# MCU_64.net
KiCad netlist of a schematic drawn in Altium Designer
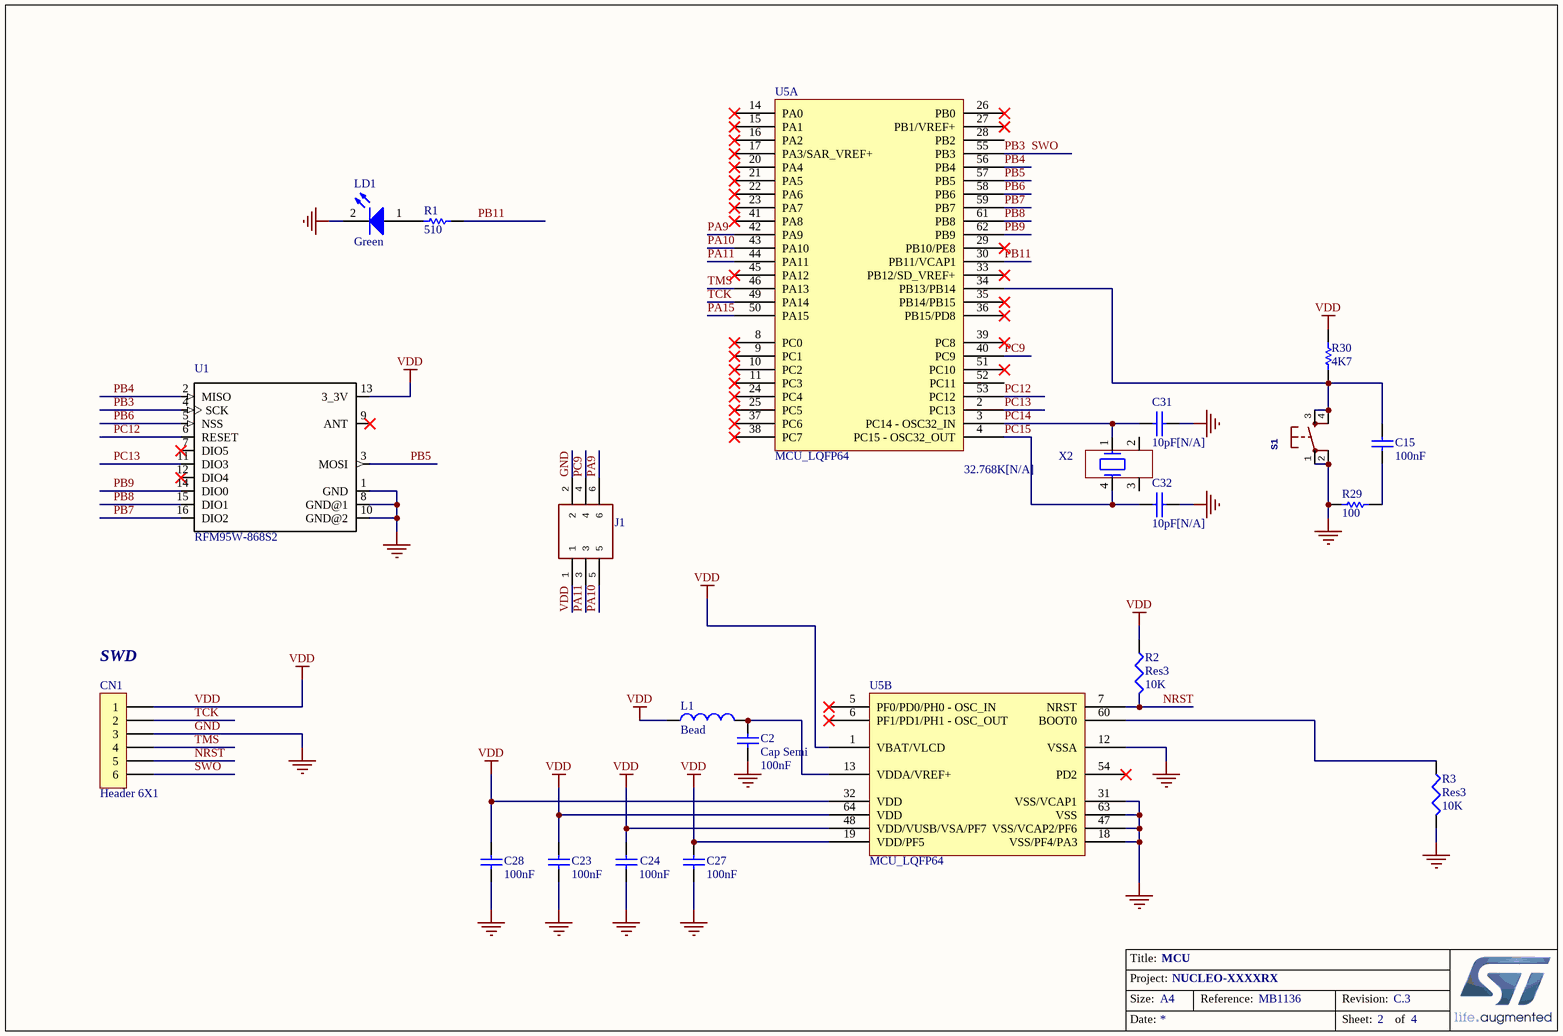
[diagram p0: MCU_64.SchDoc]

(export (version "E")
  (design (tool "Eeschema 10.0.6"))
  (components
    (comp (ref "C2")
      (value "Cap Semi")
      (footprint "1608[0603]")
      (description "Capacitor (Semiconductor SIM Model)")
      (fields (field (name "ALTIUM_VALUE") "100nF") (field (name "PUBLISHER") "Altium Limited"))
      (libsource (lib "Miscellaneous Devices") (part "Cap Semi"))
    )
    (comp (ref "C15")
      (value "100nF")
      (footprint "RAD-0.3")
      (description "Capacitor")
      (fields (field (name "PUBLISHER") "Altium Limited"))
      (libsource (lib "Miscellaneous Devices") (part "CAP"))
    )
    (comp (ref "C23")
      (value "100nF")
      (footprint "0603C")
      (description "Capacitor")
      (fields (field (name "PUBLISHER") "Altium Limited"))
      (libsource (lib "Miscellaneous Devices") (part "Cap"))
    )
    (comp (ref "C24")
      (value "100nF")
      (footprint "0603C")
      (description "Capacitor")
      (fields (field (name "PUBLISHER") "Altium Limited"))
      (libsource (lib "Miscellaneous Devices") (part "Cap"))
    )
    (comp (ref "C27")
      (value "100nF")
      (footprint "0603C")
      (description "Capacitor")
      (fields (field (name "PUBLISHER") "Altium Limited"))
      (libsource (lib "Miscellaneous Devices") (part "Cap"))
    )
    (comp (ref "C28")
      (value "100nF")
      (footprint "0603C")
      (description "Capacitor")
      (fields (field (name "PUBLISHER") "Altium Limited"))
      (libsource (lib "Miscellaneous Devices") (part "Cap"))
    )
    (comp (ref "C31")
      (value "10pF[N/A]")
      (footprint "0603C")
      (description "Capacitor")
      (libsource (lib "*") (part "CAP"))
    )
    (comp (ref "C32")
      (value "10pF[N/A]")
      (footprint "0603C")
      (description "Capacitor")
      (libsource (lib "*") (part "CAP"))
    )
    (comp (ref "CN1")
      (value "Header 6X1")
      (footprint "1*6P")
      (description "Header, 6-Pin, Single row")
      (fields (field (name "PUBLISHER") "Altium Limited"))
      (libsource (lib "Nucleo_64") (part "Header 6X1"))
    )
    (comp (ref "J1")
      (value "PIN-HEAD-1.27MM-2X03")
      (footprint "PIN-HEAD-1.27MM-2X03")
      (libsource (lib "WSense-conn-library") (part "PIN-HEAD-1.27MM-2X03"))
    )
    (comp (ref "L1")
      (value "Bead")
      (footprint "INDC1608L")
      (description "Inductor")
      (fields (field (name "PUBLISHER") "Altium Limited"))
      (libsource (lib "Miscellaneous Devices") (part "Inductor"))
    )
    (comp (ref "LD1")
      (value "Green")
      (footprint "0603D")
      (description "Typical RED, GREEN, YELLOW, AMBER GaAs LED")
      (fields (field (name "PUBLISHER") "Altium Limited"))
      (libsource (lib "Miscellaneous Devices") (part "LED2"))
    )
    (comp (ref "R1")
      (value "510")
      (footprint "0603R")
      (description "Resistor")
      (fields (field (name "PUBLISHER") "Altium Limited"))
      (libsource (lib "Miscellaneous Devices") (part "Res1"))
    )
    (comp (ref "R2")
      (value "Res3")
      (footprint "J1-0603")
      (description "Resistor")
      (fields (field (name "ALTIUM_VALUE") "10K") (field (name "PUBLISHER") "Altium Limited"))
      (libsource (lib "Miscellaneous Devices") (part "Res3"))
    )
    (comp (ref "R3")
      (value "Res3")
      (footprint "J1-0603")
      (description "Resistor")
      (fields (field (name "ALTIUM_VALUE") "10K") (field (name "PUBLISHER") "Altium Limited"))
      (libsource (lib "Miscellaneous Devices") (part "Res3"))
    )
    (comp (ref "R29")
      (value "100")
      (footprint "0603R")
      (description "Resistor")
      (fields (field (name "PUBLISHER") "Altium Limited"))
      (libsource (lib "Miscellaneous Devices") (part "Res1"))
    )
    (comp (ref "R30")
      (value "4K7")
      (footprint "0603R")
      (description "Resistor")
      (fields (field (name "PUBLISHER") "Altium Limited"))
      (libsource (lib "Miscellaneous Devices") (part "res1"))
    )
    (comp (ref "S1")
      (value "~")
      (footprint "TACTILE_SWITCH_SMD")
      (libsource (lib "WSense-conn-library") (part "TAC_SWITCHSND"))
    )
    (comp (ref "U1")
      (value "RFM95W-868S2")
      (footprint "XCVR_RFM95W-868S2")
      (fields (field (name "MF") "Hope Microelectronics"))
      (libsource (lib "RFM95W-868S2") (part "RFM95W-868S2"))
    )
    (comp (ref "U5")
      (value "MCU_LQFP64")
      (footprint "LQFP64")
      (libsource (lib "Nucleo_64") (part "MCU_LQFP64"))
    )
    (comp (ref "X2") (value "32.768K[N/A]") (footprint "XTAL_4SM_8X3R8") (libsource (lib "*") (part "MC306")))
  )
  (nets
    (net (code "1") (name "/NRST") (class "Default")
      (node (ref "CN1") (pin "5") (pinfunction "5_5") (pintype "passive"))
      (node (ref "R2") (pin "2") (pinfunction "2_2") (pintype "passive"))
      (node (ref "U5") (pin "7") (pinfunction "NRST_7") (pintype "passive"))
    )
    (net (code "2") (name "/PA9") (class "Default")
      (node (ref "J1") (pin "6") (pinfunction "6_6") (pintype "passive"))
      (node (ref "U5") (pin "42") (pinfunction "PA9_42") (pintype "passive"))
    )
    (net (code "3") (name "/PA10") (class "Default")
      (node (ref "J1") (pin "5") (pinfunction "5_5") (pintype "passive"))
      (node (ref "U5") (pin "43") (pinfunction "PA10_43") (pintype "passive"))
    )
    (net (code "4") (name "/PA11") (class "Default")
      (node (ref "J1") (pin "3") (pinfunction "3_3") (pintype "passive"))
      (node (ref "U5") (pin "44") (pinfunction "PA11_44") (pintype "passive"))
    )
    (net (code "5") (name "/PA15") (class "Default")
      (node (ref "U5") (pin "50") (pinfunction "PA15_50") (pintype "passive"))
    )
    (net (code "6") (name "/PB3") (class "Default")
      (node (ref "CN1") (pin "6") (pinfunction "6_6") (pintype "passive"))
      (node (ref "U1") (pin "4") (pinfunction "SCK_4") (pintype "input"))
      (node (ref "U5") (pin "55") (pinfunction "PB3_55") (pintype "passive"))
    )
    (net (code "7") (name "/PB4") (class "Default")
      (node (ref "U1") (pin "2") (pinfunction "MISO_2") (pintype "input"))
      (node (ref "U5") (pin "56") (pinfunction "PB4_56") (pintype "passive"))
    )
    (net (code "8") (name "/PB5") (class "Default")
      (node (ref "U1") (pin "3") (pinfunction "MOSI_3") (pintype "output"))
      (node (ref "U5") (pin "57") (pinfunction "PB5_57") (pintype "passive"))
    )
    (net (code "9") (name "/PB6") (class "Default")
      (node (ref "U1") (pin "5") (pinfunction "NSS_5") (pintype "input"))
      (node (ref "U5") (pin "58") (pinfunction "PB6_58") (pintype "passive"))
    )
    (net (code "10") (name "/PB7") (class "Default")
      (node (ref "U1") (pin "16") (pinfunction "DIO2_16") (pintype "bidirectional"))
      (node (ref "U5") (pin "59") (pinfunction "PB7_59") (pintype "passive"))
    )
    (net (code "11") (name "/PB8") (class "Default")
      (node (ref "U1") (pin "15") (pinfunction "DIO1_15") (pintype "bidirectional"))
      (node (ref "U5") (pin "61") (pinfunction "PB8_61") (pintype "passive"))
    )
    (net (code "12") (name "/PB9") (class "Default")
      (node (ref "U1") (pin "14") (pinfunction "DIO0_14") (pintype "bidirectional"))
      (node (ref "U5") (pin "62") (pinfunction "PB9_62") (pintype "passive"))
    )
    (net (code "13") (name "/PB11") (class "Default")
      (node (ref "R1") (pin "1") (pinfunction "1_1") (pintype "passive"))
      (node (ref "U5") (pin "30") (pinfunction "PB11/VCAP1_30") (pintype "passive"))
    )
    (net (code "14") (name "/PC9") (class "Default")
      (node (ref "J1") (pin "4") (pinfunction "4_4") (pintype "passive"))
      (node (ref "U5") (pin "40") (pinfunction "PC9_40") (pintype "passive"))
    )
    (net (code "15") (name "/PC12") (class "Default")
      (node (ref "U1") (pin "6") (pinfunction "RESET_6") (pintype "bidirectional"))
      (node (ref "U5") (pin "53") (pinfunction "PC12_53") (pintype "passive"))
    )
    (net (code "16") (name "/PC13") (class "Default")
      (node (ref "U1") (pin "11") (pinfunction "DIO3_11") (pintype "bidirectional"))
      (node (ref "U5") (pin "2") (pinfunction "PC13_2") (pintype "passive"))
    )
    (net (code "17") (name "/PC14") (class "Default")
      (node (ref "C31") (pin "1") (pinfunction "1_1") (pintype "passive"))
      (node (ref "U5") (pin "3") (pinfunction "PC14_-_OSC32_IN_3") (pintype "passive"))
      (node (ref "X2") (pin "1") (pinfunction "1_1") (pintype "passive"))
    )
    (net (code "18") (name "/PC15") (class "Default")
      (node (ref "C32") (pin "1") (pinfunction "1_1") (pintype "passive"))
      (node (ref "U5") (pin "4") (pinfunction "PC15_-_OSC32_OUT_4") (pintype "passive"))
      (node (ref "X2") (pin "4") (pinfunction "4_4") (pintype "passive"))
    )
    (net (code "19") (name "/TCK") (class "Default")
      (node (ref "CN1") (pin "2") (pinfunction "2_2") (pintype "passive"))
      (node (ref "U5") (pin "49") (pinfunction "PA14_49") (pintype "passive"))
    )
    (net (code "20") (name "/TMS") (class "Default")
      (node (ref "CN1") (pin "4") (pinfunction "4_4") (pintype "passive"))
      (node (ref "U5") (pin "46") (pinfunction "PA13_46") (pintype "passive"))
    )
    (net (code "21") (name "GND") (class "Default")
      (node (ref "C2") (pin "2") (pinfunction "2_2") (pintype "passive"))
      (node (ref "C23") (pin "2") (pinfunction "2_2") (pintype "passive"))
      (node (ref "C24") (pin "2") (pinfunction "2_2") (pintype "passive"))
      (node (ref "C27") (pin "2") (pinfunction "2_2") (pintype "passive"))
      (node (ref "C28") (pin "2") (pinfunction "2_2") (pintype "passive"))
      (node (ref "C31") (pin "2") (pinfunction "2_2") (pintype "passive"))
      (node (ref "C32") (pin "2") (pinfunction "2_2") (pintype "passive"))
      (node (ref "CN1") (pin "3") (pinfunction "3_3") (pintype "passive"))
      (node (ref "J1") (pin "2") (pinfunction "2_2") (pintype "passive"))
      (node (ref "LD1") (pin "2") (pinfunction "K_2") (pintype "passive"))
      (node (ref "R29") (pin "1") (pinfunction "1_1") (pintype "passive"))
      (node (ref "R3") (pin "2") (pinfunction "2_2") (pintype "passive"))
      (node (ref "S1") (pin "1") (pinfunction "1_1") (pintype "passive"))
      (node (ref "S1") (pin "2") (pinfunction "2_2") (pintype "passive"))
      (node (ref "U1") (pin "1") (pinfunction "GND_1") (pintype "power_in"))
      (node (ref "U1") (pin "10") (pinfunction "GND@2_10") (pintype "power_in"))
      (node (ref "U1") (pin "8") (pinfunction "GND@1_8") (pintype "power_in"))
      (node (ref "U5") (pin "12") (pinfunction "VSSA_12") (pintype "passive"))
      (node (ref "U5") (pin "18") (pinfunction "VSS/PF4/PA3_18") (pintype "passive"))
      (node (ref "U5") (pin "31") (pinfunction "VSS/VCAP1_31") (pintype "passive"))
      (node (ref "U5") (pin "47") (pinfunction "VSS/VCAP2/PF6_47") (pintype "passive"))
      (node (ref "U5") (pin "63") (pinfunction "VSS_63") (pintype "passive"))
    )
    (net (code "22") (name "Net-(C15-Pad1)") (class "Default")
      (node (ref "C15") (pin "1") (pinfunction "1_1") (pintype "passive"))
      (node (ref "R29") (pin "2") (pinfunction "2_2") (pintype "passive"))
    )
    (net (code "23") (name "Net-(LD1-A)") (class "Default")
      (node (ref "LD1") (pin "1") (pinfunction "A_1") (pintype "passive"))
      (node (ref "R1") (pin "2") (pinfunction "2_2") (pintype "passive"))
    )
    (net (code "24") (name "Net-(U5A-PB13{slash}PB14)") (class "Default")
      (node (ref "C15") (pin "2") (pinfunction "2_2") (pintype "passive"))
      (node (ref "R30") (pin "1") (pinfunction "1_1") (pintype "passive"))
      (node (ref "S1") (pin "3") (pinfunction "3_3") (pintype "passive"))
      (node (ref "S1") (pin "4") (pinfunction "4_4") (pintype "passive"))
      (node (ref "U5") (pin "34") (pinfunction "PB13/PB14_34") (pintype "passive"))
    )
    (net (code "25") (name "Net-(U5B-BOOT0)") (class "Default")
      (node (ref "R3") (pin "1") (pinfunction "1_1") (pintype "passive"))
      (node (ref "U5") (pin "60") (pinfunction "BOOT0_60") (pintype "passive"))
    )
    (net (code "26") (name "Net-(U5B-VDDA{slash}VREF+)") (class "Default")
      (node (ref "C2") (pin "1") (pinfunction "1_1") (pintype "passive"))
      (node (ref "L1") (pin "2") (pinfunction "2_2") (pintype "passive"))
      (node (ref "U5") (pin "13") (pinfunction "VDDA/VREF+_13") (pintype "passive"))
    )
    (net (code "27") (name "VDD") (class "Default")
      (node (ref "C23") (pin "1") (pinfunction "1_1") (pintype "passive"))
      (node (ref "C24") (pin "1") (pinfunction "1_1") (pintype "passive"))
      (node (ref "C27") (pin "1") (pinfunction "1_1") (pintype "passive"))
      (node (ref "C28") (pin "1") (pinfunction "1_1") (pintype "passive"))
      (node (ref "CN1") (pin "1") (pinfunction "1_1") (pintype "passive"))
      (node (ref "J1") (pin "1") (pinfunction "1_1") (pintype "passive"))
      (node (ref "L1") (pin "1") (pinfunction "1_1") (pintype "passive"))
      (node (ref "R2") (pin "1") (pinfunction "1_1") (pintype "passive"))
      (node (ref "R30") (pin "2") (pinfunction "2_2") (pintype "passive"))
      (node (ref "U1") (pin "13") (pinfunction "3_3V_13") (pintype "power_in"))
      (node (ref "U5") (pin "1") (pinfunction "VBAT/VLCD_1") (pintype "passive"))
      (node (ref "U5") (pin "19") (pinfunction "VDD/PF5_19") (pintype "passive"))
      (node (ref "U5") (pin "32") (pinfunction "VDD_32") (pintype "passive"))
      (node (ref "U5") (pin "48") (pinfunction "VDD/VUSB/VSA/PF7_48") (pintype "passive"))
      (node (ref "U5") (pin "64") (pinfunction "VDD_64") (pintype "passive"))
    )
    (net (code "28") (name "unconnected-(U1-ANT-Pad9)") (class "Default")
      (node (ref "U1") (pin "9") (pinfunction "ANT_9") (pintype "passive+no_connect"))
    )
    (net (code "29") (name "unconnected-(U1-DIO4-Pad12)") (class "Default")
      (node (ref "U1") (pin "12") (pinfunction "DIO4_12") (pintype "bidirectional+no_connect"))
    )
    (net (code "30") (name "unconnected-(U1-DIO5-Pad7)") (class "Default")
      (node (ref "U1") (pin "7") (pinfunction "DIO5_7") (pintype "bidirectional+no_connect"))
    )
    (net (code "31") (name "unconnected-(U5A-PA0-Pad14)") (class "Default")
      (node (ref "U5") (pin "14") (pinfunction "PA0_14") (pintype "passive+no_connect"))
    )
    (net (code "32") (name "unconnected-(U5A-PA1-Pad15)") (class "Default")
      (node (ref "U5") (pin "15") (pinfunction "PA1_15") (pintype "passive+no_connect"))
    )
    (net (code "33") (name "unconnected-(U5A-PA2-Pad16)") (class "Default")
      (node (ref "U5") (pin "16") (pinfunction "PA2_16") (pintype "passive+no_connect"))
    )
    (net (code "34") (name "unconnected-(U5A-PA3{slash}SAR_VREF+-Pad17)") (class "Default")
      (node (ref "U5") (pin "17") (pinfunction "PA3/SAR_VREF+_17") (pintype "passive+no_connect"))
    )
    (net (code "35") (name "unconnected-(U5A-PA4-Pad20)") (class "Default")
      (node (ref "U5") (pin "20") (pinfunction "PA4_20") (pintype "passive+no_connect"))
    )
    (net (code "36") (name "unconnected-(U5A-PA5-Pad21)") (class "Default")
      (node (ref "U5") (pin "21") (pinfunction "PA5_21") (pintype "passive+no_connect"))
    )
    (net (code "37") (name "unconnected-(U5A-PA6-Pad22)") (class "Default")
      (node (ref "U5") (pin "22") (pinfunction "PA6_22") (pintype "passive+no_connect"))
    )
    (net (code "38") (name "unconnected-(U5A-PA7-Pad23)") (class "Default")
      (node (ref "U5") (pin "23") (pinfunction "PA7_23") (pintype "passive+no_connect"))
    )
    (net (code "39") (name "unconnected-(U5A-PA8-Pad41)") (class "Default")
      (node (ref "U5") (pin "41") (pinfunction "PA8_41") (pintype "passive+no_connect"))
    )
    (net (code "40") (name "unconnected-(U5A-PA12-Pad45)") (class "Default")
      (node (ref "U5") (pin "45") (pinfunction "PA12_45") (pintype "passive+no_connect"))
    )
    (net (code "41") (name "unconnected-(U5A-PB0-Pad26)") (class "Default")
      (node (ref "U5") (pin "26") (pinfunction "PB0_26") (pintype "passive+no_connect"))
    )
    (net (code "42") (name "unconnected-(U5A-PB1{slash}VREF+-Pad27)") (class "Default")
      (node (ref "U5") (pin "27") (pinfunction "PB1/VREF+_27") (pintype "passive+no_connect"))
    )
    (net (code "43") (name "unconnected-(U5A-PB2-Pad28)") (class "Default")
      (node (ref "U5") (pin "28") (pinfunction "PB2_28") (pintype "passive"))
    )
    (net (code "44") (name "unconnected-(U5A-PB10{slash}PE8-Pad29)") (class "Default")
      (node (ref "U5") (pin "29") (pinfunction "PB10/PE8_29") (pintype "passive+no_connect"))
    )
    (net (code "45") (name "unconnected-(U5A-PB12{slash}SD_VREF+-Pad33)") (class "Default")
      (node (ref "U5") (pin "33") (pinfunction "PB12/SD_VREF+_33") (pintype "passive+no_connect"))
    )
    (net (code "46") (name "unconnected-(U5A-PB14{slash}PB15-Pad35)") (class "Default")
      (node (ref "U5") (pin "35") (pinfunction "PB14/PB15_35") (pintype "passive+no_connect"))
    )
    (net (code "47") (name "unconnected-(U5A-PB15{slash}PD8-Pad36)") (class "Default")
      (node (ref "U5") (pin "36") (pinfunction "PB15/PD8_36") (pintype "passive+no_connect"))
    )
    (net (code "48") (name "unconnected-(U5A-PC0-Pad8)") (class "Default")
      (node (ref "U5") (pin "8") (pinfunction "PC0_8") (pintype "passive+no_connect"))
    )
    (net (code "49") (name "unconnected-(U5A-PC1-Pad9)") (class "Default")
      (node (ref "U5") (pin "9") (pinfunction "PC1_9") (pintype "passive+no_connect"))
    )
    (net (code "50") (name "unconnected-(U5A-PC2-Pad10)") (class "Default")
      (node (ref "U5") (pin "10") (pinfunction "PC2_10") (pintype "passive+no_connect"))
    )
    (net (code "51") (name "unconnected-(U5A-PC3-Pad11)") (class "Default")
      (node (ref "U5") (pin "11") (pinfunction "PC3_11") (pintype "passive+no_connect"))
    )
    (net (code "52") (name "unconnected-(U5A-PC4-Pad24)") (class "Default")
      (node (ref "U5") (pin "24") (pinfunction "PC4_24") (pintype "passive+no_connect"))
    )
    (net (code "53") (name "unconnected-(U5A-PC5-Pad25)") (class "Default")
      (node (ref "U5") (pin "25") (pinfunction "PC5_25") (pintype "passive+no_connect"))
    )
    (net (code "54") (name "unconnected-(U5A-PC6-Pad37)") (class "Default")
      (node (ref "U5") (pin "37") (pinfunction "PC6_37") (pintype "passive+no_connect"))
    )
    (net (code "55") (name "unconnected-(U5A-PC7-Pad38)") (class "Default")
      (node (ref "U5") (pin "38") (pinfunction "PC7_38") (pintype "passive+no_connect"))
    )
    (net (code "56") (name "unconnected-(U5A-PC8-Pad39)") (class "Default")
      (node (ref "U5") (pin "39") (pinfunction "PC8_39") (pintype "passive+no_connect"))
    )
    (net (code "57") (name "unconnected-(U5A-PC10-Pad51)") (class "Default")
      (node (ref "U5") (pin "51") (pinfunction "PC10_51") (pintype "passive+no_connect"))
    )
    (net (code "58") (name "unconnected-(U5A-PC11-Pad52)") (class "Default")
      (node (ref "U5") (pin "52") (pinfunction "PC11_52") (pintype "passive"))
    )
    (net (code "59") (name "unconnected-(U5B-PD2-Pad54)") (class "Default")
      (node (ref "U5") (pin "54") (pinfunction "PD2_54") (pintype "passive+no_connect"))
    )
    (net (code "60") (name "unconnected-(U5B-PF0{slash}PD0{slash}PH0_-_OSC_IN-Pad5)") (class "Default")
      (node (ref "U5") (pin "5") (pinfunction "PF0/PD0/PH0_-_OSC_IN_5") (pintype "passive+no_connect"))
    )
    (net (code "61") (name "unconnected-(U5B-PF1{slash}PD1{slash}PH1_-_OSC_OUT-Pad6)") (class "Default")
      (node (ref "U5") (pin "6") (pinfunction "PF1/PD1/PH1_-_OSC_OUT_6") (pintype "passive+no_connect"))
    )
    (net (code "62") (name "unconnected-(X2-Pad2)") (class "Default")
      (node (ref "X2") (pin "2") (pinfunction "2_2") (pintype "passive"))
    )
    (net (code "63") (name "unconnected-(X2-Pad3)") (class "Default")
      (node (ref "X2") (pin "3") (pinfunction "3_3") (pintype "passive"))
    )
  )
)
